# M8-ucam.net
KiCad netlist of a schematic drawn in EAGLE
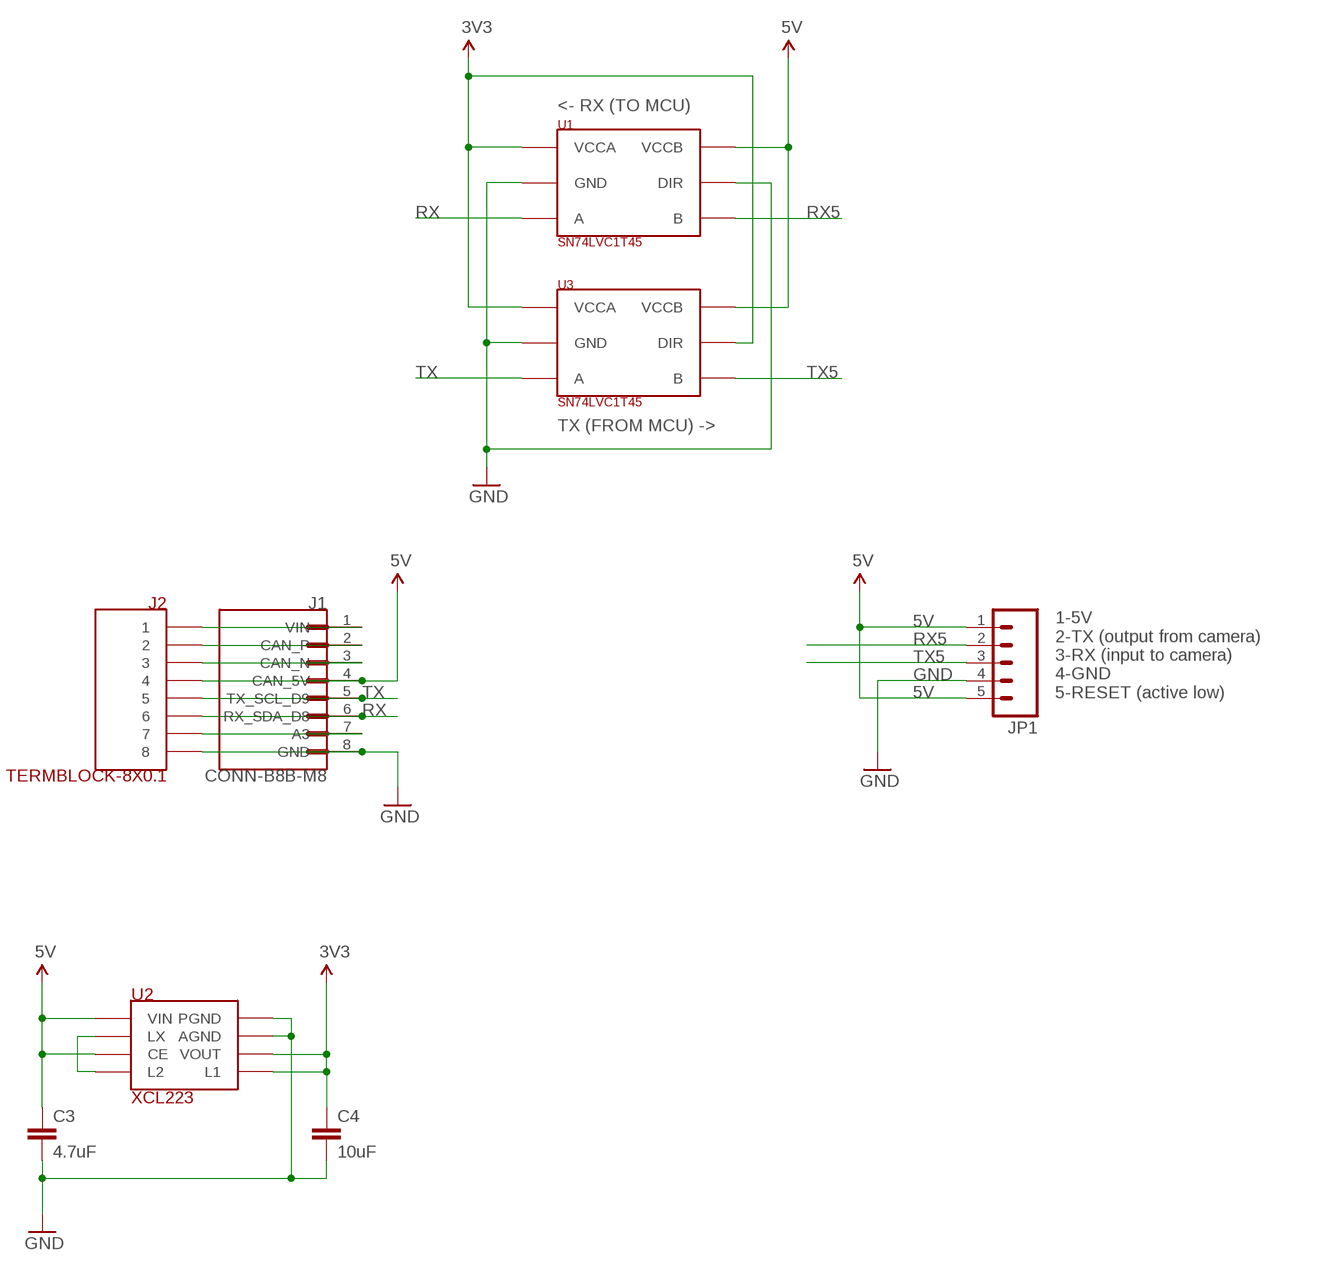
[diagram p0: schematic, sheet 1]

(export (version "E")
  (design (tool "Eeschema 10.0.6"))
  (components
    (comp (ref "C3")
      (value "4.7uF")
      (footprint "eagle-import:0603-CAP")
      (libsource (lib "eagle-import") (part "CAP-4.7UF-0603"))
    )
    (comp (ref "C4")
      (value "10uF")
      (footprint "eagle-import:0603-CAP")
      (libsource (lib "eagle-import") (part "CAP-10UF-0603"))
    )
    (comp (ref "J1")
      (value "CONN-B8B-M8")
      (footprint "eagle-import:JST_B8B-PH-SM4-TB(LF)(SN)")
      (libsource (lib "eagle-import") (part "CONN-B8B-M8"))
    )
    (comp (ref "J2")
      (value "TERMBLOCK-8X0.1")
      (footprint "eagle-import:TERMBLOCK-8X0.1")
      (libsource (lib "eagle-import") (part "TERMBLOCK-8X0.1"))
    )
    (comp (ref "JP1")
      (value "M05PTH")
      (footprint "eagle-import:1X05")
      (libsource (lib "eagle-import") (part "M05PTH"))
    )
    (comp (ref "U1")
      (value "SN74LVC1T45")
      (footprint "eagle-import:SC70-TI")
      (libsource (lib "eagle-import") (part "SN74LVC1T45"))
    )
    (comp (ref "U2")
      (value "XCL223")
      (footprint "eagle-import:REG-XCL223-LESS-CREAM")
      (libsource (lib "eagle-import") (part "REG-XCL223"))
    )
    (comp (ref "U3")
      (value "SN74LVC1T45")
      (footprint "eagle-import:SC70-TI")
      (libsource (lib "eagle-import") (part "SN74LVC1T45"))
    )
  )
  (nets
    (net (code "1") (name "/RX") (class "Default")
      (node (ref "J1") (pin "6") (pinfunction "RX_SDA_D8_6") (pintype "passive"))
      (node (ref "J2") (pin "P$6") (pinfunction "6_P$6") (pintype "passive"))
      (node (ref "U1") (pin "3") (pinfunction "A_3") (pintype "bidirectional"))
    )
    (net (code "2") (name "/RX5") (class "Default")
      (node (ref "JP1") (pin "2") (pinfunction "2_2") (pintype "passive"))
      (node (ref "U1") (pin "4") (pinfunction "B_4") (pintype "bidirectional"))
    )
    (net (code "3") (name "/TX") (class "Default")
      (node (ref "J1") (pin "5") (pinfunction "TX_SCL_D9_5") (pintype "passive"))
      (node (ref "J2") (pin "P$5") (pinfunction "5_P$5") (pintype "passive"))
      (node (ref "U3") (pin "3") (pinfunction "A_3") (pintype "bidirectional"))
    )
    (net (code "4") (name "/TX5") (class "Default")
      (node (ref "JP1") (pin "3") (pinfunction "3_3") (pintype "passive"))
      (node (ref "U3") (pin "4") (pinfunction "B_4") (pintype "bidirectional"))
    )
    (net (code "5") (name "3V3") (class "Default")
      (node (ref "C4") (pin "1") (pinfunction "1_1") (pintype "passive"))
      (node (ref "U1") (pin "1") (pinfunction "VCCA_1") (pintype "power_in"))
      (node (ref "U2") (pin "3") (pinfunction "VOUT_3") (pintype "passive"))
      (node (ref "U2") (pin "7") (pinfunction "L1_7") (pintype "passive"))
      (node (ref "U3") (pin "1") (pinfunction "VCCA_1") (pintype "power_in"))
      (node (ref "U3") (pin "5") (pinfunction "DIR_5") (pintype "input"))
    )
    (net (code "6") (name "5V") (class "Default")
      (node (ref "C3") (pin "1") (pinfunction "1_1") (pintype "passive"))
      (node (ref "J1") (pin "4") (pinfunction "CAN_5V_4") (pintype "passive"))
      (node (ref "J2") (pin "P$4") (pinfunction "4_P$4") (pintype "passive"))
      (node (ref "JP1") (pin "1") (pinfunction "1_1") (pintype "passive"))
      (node (ref "JP1") (pin "5") (pinfunction "5_5") (pintype "passive"))
      (node (ref "U1") (pin "6") (pinfunction "VCCB_6") (pintype "power_in"))
      (node (ref "U2") (pin "4") (pinfunction "CE_4") (pintype "input"))
      (node (ref "U2") (pin "6") (pinfunction "VIN_6") (pintype "power_in"))
      (node (ref "U3") (pin "6") (pinfunction "VCCB_6") (pintype "power_in"))
    )
    (net (code "7") (name "GND") (class "Default")
      (node (ref "C3") (pin "2") (pinfunction "2_2") (pintype "passive"))
      (node (ref "C4") (pin "2") (pinfunction "2_2") (pintype "passive"))
      (node (ref "J1") (pin "8") (pinfunction "GND_8") (pintype "passive"))
      (node (ref "J2") (pin "P$8") (pinfunction "8_P$8") (pintype "passive"))
      (node (ref "JP1") (pin "4") (pinfunction "4_4") (pintype "passive"))
      (node (ref "U1") (pin "2") (pinfunction "GND_2") (pintype "power_in"))
      (node (ref "U1") (pin "5") (pinfunction "DIR_5") (pintype "input"))
      (node (ref "U2") (pin "1") (pinfunction "PGND_1") (pintype "passive"))
      (node (ref "U2") (pin "2") (pinfunction "AGND_2") (pintype "passive"))
      (node (ref "U3") (pin "2") (pinfunction "GND_2") (pintype "power_in"))
    )
    (net (code "8") (name "Net-(J1-A3)") (class "Default")
      (node (ref "J1") (pin "7") (pinfunction "A3_7") (pintype "passive"))
      (node (ref "J2") (pin "P$7") (pinfunction "7_P$7") (pintype "passive"))
    )
    (net (code "9") (name "Net-(J1-CAN_N)") (class "Default")
      (node (ref "J1") (pin "3") (pinfunction "CAN_N_3") (pintype "passive"))
      (node (ref "J2") (pin "P$3") (pinfunction "3_P$3") (pintype "passive"))
    )
    (net (code "10") (name "Net-(J1-CAN_P)") (class "Default")
      (node (ref "J1") (pin "2") (pinfunction "CAN_P_2") (pintype "passive"))
      (node (ref "J2") (pin "P$2") (pinfunction "2_P$2") (pintype "passive"))
    )
    (net (code "11") (name "Net-(J1-VIN)") (class "Default")
      (node (ref "J1") (pin "1") (pinfunction "VIN_1") (pintype "passive"))
      (node (ref "J2") (pin "P$1") (pinfunction "1_P$1") (pintype "passive"))
    )
    (net (code "12") (name "Net-(U2-L2)") (class "Default")
      (node (ref "U2") (pin "5") (pinfunction "LX_5") (pintype "passive"))
      (node (ref "U2") (pin "8") (pinfunction "L2_8") (pintype "passive"))
    )
  )
)
